# S6XT10W_MCU.net
KiCad netlist of a schematic drawn in Altium Designer
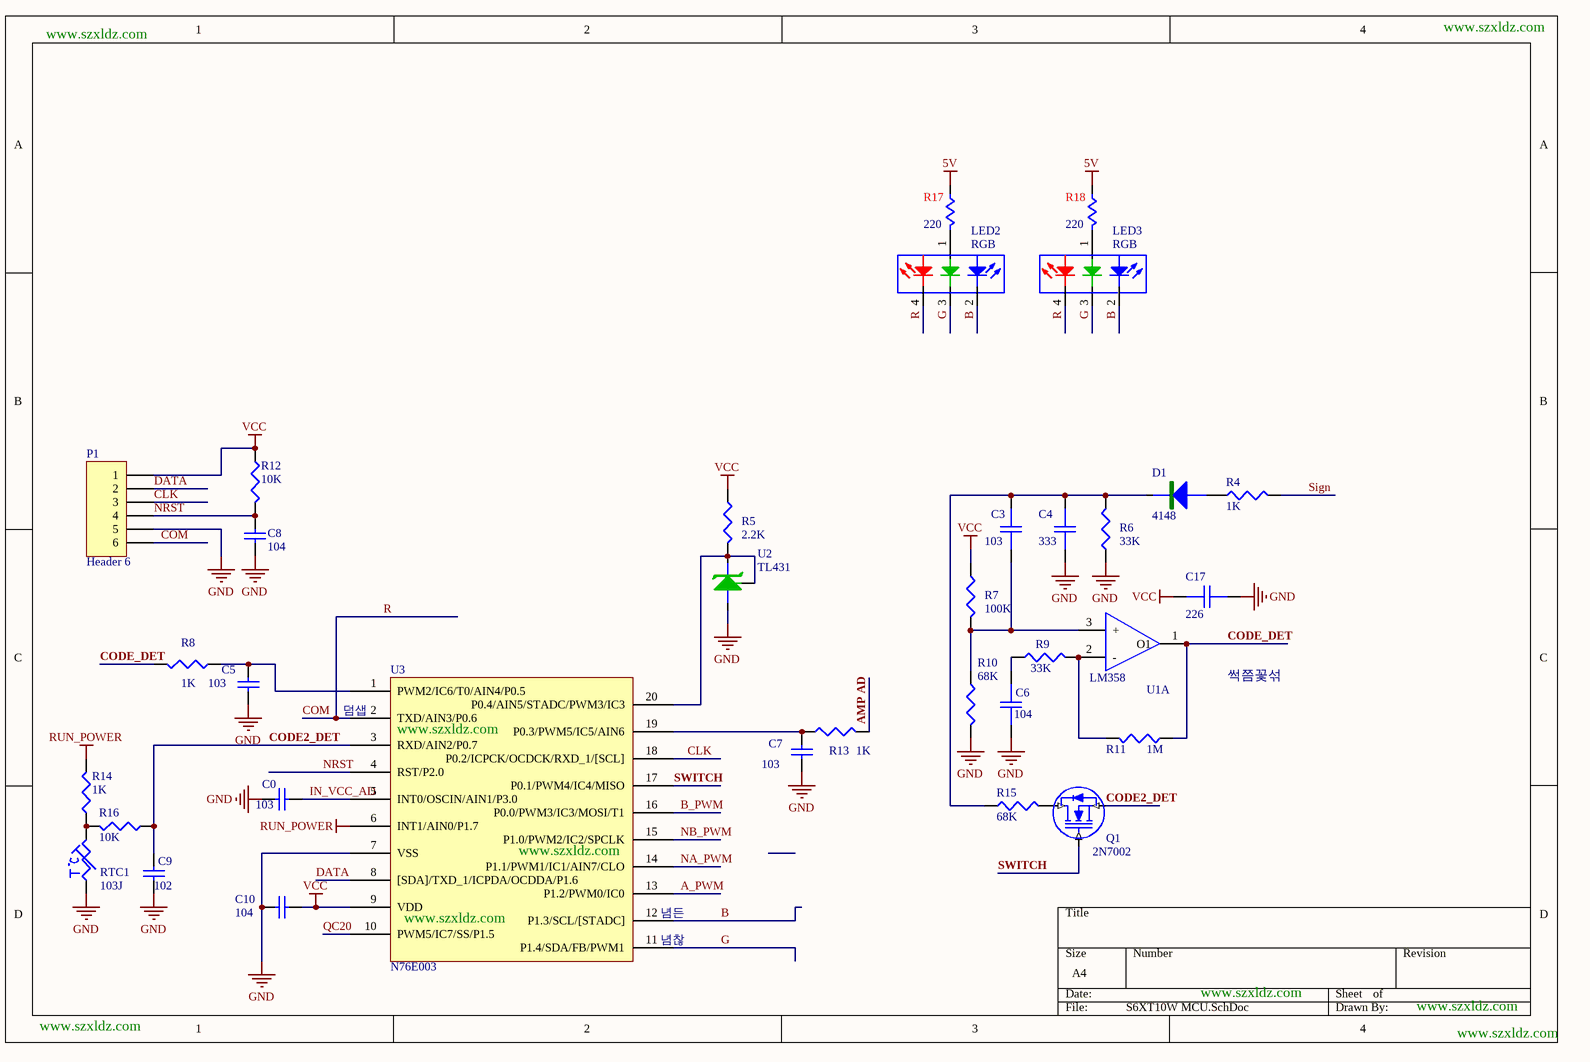
[diagram p0: S6XT10W MCU.SchDoc]

(export (version "E")
  (design (tool "Eeschema 10.0.6"))
  (components
    (comp (ref "C0")
      (value "103")
      (footprint "C0402")
      (description "Capacitor")
      (fields (field (name "PUBLISHER") "Altium Limited"))
      (libsource (lib "*") (part "Cap"))
    )
    (comp (ref "C3") (value "103") (footprint "C0402") (libsource (lib "*") (part "CH")))
    (comp (ref "C4") (value "333") (footprint "C0402") (libsource (lib "*") (part "CH")))
    (comp (ref "C5")
      (value "103")
      (footprint "C0402")
      (description "Capacitor")
      (fields (field (name "PUBLISHER") "Altium Limited"))
      (libsource (lib "*") (part "Cap"))
    )
    (comp (ref "C6") (value "104") (footprint "C0402") (libsource (lib "*") (part "CH")))
    (comp (ref "C7")
      (value "103")
      (footprint "C0402")
      (description "Capacitor")
      (fields (field (name "PUBLISHER") "Altium Limited"))
      (libsource (lib "*") (part "Cap"))
    )
    (comp (ref "C8")
      (value "104")
      (footprint "C0402")
      (description "Capacitor")
      (fields (field (name "PUBLISHER") "Altium Limited"))
      (libsource (lib "*") (part "Cap"))
    )
    (comp (ref "C9")
      (value "102")
      (footprint "C0402")
      (description "Capacitor")
      (fields (field (name "PUBLISHER") "Altium Limited"))
      (libsource (lib "*") (part "Cap"))
    )
    (comp (ref "C10")
      (value "104")
      (footprint "C0402")
      (description "Capacitor")
      (fields (field (name "PUBLISHER") "Altium Limited"))
      (libsource (lib "*") (part "Cap"))
    )
    (comp (ref "C17") (value "226") (footprint "C0805") (libsource (lib "*") (part "CH")))
    (comp (ref "D1")
      (value "4148")
      (footprint "sod323")
      (description "1N4001")
      (libsource (lib "*") (part "D0"))
    )
    (comp (ref "LED2") (value "RGB") (footprint "LED-RGB02") (libsource (lib "XiaoQiang") (part "LED05")))
    (comp (ref "LED3") (value "RGB") (footprint "LED-RGB02") (libsource (lib "XiaoQiang") (part "LED05")))
    (comp (ref "P1")
      (value "Header 6")
      (footprint "SPIN6")
      (description "Header, 6-Pin")
      (fields (field (name "PUBLISHER") "Altium Limited"))
      (libsource (lib "Miscellaneous Connectors") (part "Header 6"))
    )
    (comp (ref "Q1") (value "2N7002") (footprint "SOT-23B") (libsource (lib "lxzschlib") (part "MOSFETN")))
    (comp (ref "R4") (value "1K") (footprint "R0402") (libsource (lib "*") (part "R")))
    (comp (ref "R5") (value "2.2K") (footprint "R0402") (description "1K") (libsource (lib "*") (part "R")))
    (comp (ref "R6") (value "33K") (footprint "R0402") (description "1K") (libsource (lib "*") (part "R")))
    (comp (ref "R7") (value "100K") (footprint "R0402") (description "1K") (libsource (lib "*") (part "R")))
    (comp (ref "R8") (value "1K") (footprint "R0402") (libsource (lib "*") (part "R")))
    (comp (ref "R9") (value "33K") (footprint "R0402") (description "1K") (libsource (lib "*") (part "R")))
    (comp (ref "R10") (value "68K") (footprint "R0402") (description "1K") (libsource (lib "*") (part "R")))
    (comp (ref "R11") (value "1M") (footprint "R0402") (description "1K") (libsource (lib "*") (part "R")))
    (comp (ref "R12") (value "10K") (footprint "R0402") (libsource (lib "*") (part "R")))
    (comp (ref "R13") (value "1K") (footprint "R0402") (libsource (lib "*") (part "R")))
    (comp (ref "R14") (value "1K") (footprint "R0402") (libsource (lib "lxzschlib") (part "R")))
    (comp (ref "R15") (value "68K") (footprint "R0402") (description "1K") (libsource (lib "*") (part "R")))
    (comp (ref "R16")
      (value "10K")
      (footprint "R0402")
      (description "1K")
      (libsource (lib "lxzschlib") (part "R"))
    )
    (comp (ref "R17") (value "220") (footprint "R0402") (libsource (lib "XiaoQiang") (part "Res01")))
    (comp (ref "R18") (value "220") (footprint "R0402") (libsource (lib "XiaoQiang") (part "Res01")))
    (comp (ref "RTC1") (value "103J") (footprint "R0402") (libsource (lib "lxzschlib") (part "RTC")))
    (comp (ref "U1") (value "LM358") (footprint "SOP8") (libsource (lib "lxzschlib") (part "4558")))
    (comp (ref "U2")
      (value "TL431")
      (footprint "SOT-23-431")
      (description "IC")
      (libsource (lib "lxzschlib") (part "IC TL431"))
    )
    (comp (ref "U3") (value "N76E003") (footprint "SOP20") (libsource (lib "BEE802_V11") (part "103F")))
  )
  (nets
    (net (code "1") (name "/AMP AD") (class "Default") (node (ref "R13") (pin "2") (pintype "passive")))
    (net (code "2") (name "/A_PWM") (class "Default")
      (node (ref "U3") (pin "13") (pinfunction "P1.2/PWM0/IC0_13") (pintype "passive"))
    )
    (net (code "3") (name "/B") (class "Default")
      (node (ref "LED2") (pin "2") (pinfunction "A_2") (pintype "passive"))
      (node (ref "LED3") (pin "2") (pinfunction "A_2") (pintype "passive"))
      (node (ref "U3") (pin "12") (pinfunction "P1.3/SCL/[STADC]_12") (pintype "passive"))
    )
    (net (code "4") (name "/B_PWM") (class "Default")
      (node (ref "U3") (pin "16") (pinfunction "P0.0/PWM3/IC3/MOSI/T1_16") (pintype "passive"))
    )
    (net (code "5") (name "/CLK") (class "Default")
      (node (ref "P1") (pin "3") (pinfunction "3_3") (pintype "passive"))
      (node (ref "U3") (pin "18") (pinfunction "P0.2/ICPCK/OCDCK/RXD_1/[SCL]_18") (pintype "passive"))
    )
    (net (code "6") (name "/CODE2_DET") (class "Default")
      (node (ref "C9") (pin "2") (pinfunction "2_2") (pintype "passive"))
      (node (ref "Q1") (pin "E") (pinfunction "S_E") (pintype "input"))
      (node (ref "R16") (pin "1") (pintype "passive"))
      (node (ref "U3") (pin "3") (pinfunction "RXD/AIN2/P0.7_3") (pintype "passive"))
    )
    (net (code "7") (name "/CODE_DET") (class "Default")
      (node (ref "R11") (pin "1") (pintype "passive"))
      (node (ref "R8") (pin "2") (pintype "passive"))
      (node (ref "U1") (pin "1") (pinfunction "O1_1") (pintype "passive"))
    )
    (net (code "8") (name "/COM") (class "Default")
      (node (ref "LED2") (pin "4") (pinfunction "2_4") (pintype "passive"))
      (node (ref "LED3") (pin "4") (pinfunction "2_4") (pintype "passive"))
      (node (ref "P1") (pin "6") (pinfunction "6_6") (pintype "passive"))
      (node (ref "U3") (pin "2") (pinfunction "TXD/AIN3/P0.6_2") (pintype "passive"))
    )
    (net (code "9") (name "/DATA") (class "Default")
      (node (ref "P1") (pin "2") (pinfunction "2_2") (pintype "passive"))
      (node (ref "U3") (pin "8") (pinfunction "[SDA]/TXD_1/ICPDA/OCDDA/P1.6_8") (pintype "passive"))
    )
    (net (code "10") (name "/G") (class "Default")
      (node (ref "LED2") (pin "3") (pinfunction "2_3") (pintype "passive"))
      (node (ref "LED3") (pin "3") (pinfunction "2_3") (pintype "passive"))
      (node (ref "U3") (pin "11") (pinfunction "P1.4/SDA/FB/PWM1_11") (pintype "passive"))
    )
    (net (code "11") (name "/IN_VCC_AD") (class "Default")
      (node (ref "C0") (pin "2") (pinfunction "2_2") (pintype "passive"))
      (node (ref "U3") (pin "5") (pinfunction "INT0/OSCIN/AIN1/P3.0_5") (pintype "passive"))
    )
    (net (code "12") (name "/NA_PWM") (class "Default")
      (node (ref "U3") (pin "14") (pinfunction "P1.1/PWM1/IC1/AIN7/CLO_14") (pintype "passive"))
    )
    (net (code "13") (name "/NB_PWM") (class "Default")
      (node (ref "U3") (pin "15") (pinfunction "P1.0/PWM2/IC2/SPCLK_15") (pintype "passive"))
    )
    (net (code "14") (name "/NRST") (class "Default")
      (node (ref "C8") (pin "1") (pinfunction "1_1") (pintype "passive"))
      (node (ref "P1") (pin "4") (pinfunction "4_4") (pintype "passive"))
      (node (ref "R12") (pin "2") (pintype "passive"))
      (node (ref "U3") (pin "4") (pinfunction "RST/P2.0_4") (pintype "passive"))
    )
    (net (code "15") (name "/QC20") (class "Default")
      (node (ref "U3") (pin "10") (pinfunction "PWM5/IC7/SS/P1.5_10") (pintype "passive"))
    )
    (net (code "16") (name "/SWITCH") (class "Default")
      (node (ref "Q1") (pin "B") (pinfunction "G_B") (pintype "input"))
      (node (ref "U3") (pin "17") (pinfunction "P0.1/PWM4/IC4/MISO_17") (pintype "passive"))
    )
    (net (code "17") (name "/Sign") (class "Default") (node (ref "R4") (pin "2") (pintype "passive")))
    (net (code "18") (name "5V") (class "Default")
      (node (ref "R17") (pin "1") (pinfunction "1_1") (pintype "passive"))
      (node (ref "R18") (pin "1") (pinfunction "1_1") (pintype "passive"))
    )
    (net (code "19") (name "GND") (class "Default")
      (node (ref "C0") (pin "1") (pinfunction "1_1") (pintype "passive"))
      (node (ref "C10") (pin "1") (pinfunction "1_1") (pintype "passive"))
      (node (ref "C17") (pin "1") (pintype "passive"))
      (node (ref "C4") (pin "1") (pintype "passive"))
      (node (ref "C5") (pin "1") (pinfunction "1_1") (pintype "passive"))
      (node (ref "C6") (pin "1") (pintype "passive"))
      (node (ref "C7") (pin "2") (pinfunction "2_2") (pintype "passive"))
      (node (ref "C8") (pin "2") (pinfunction "2_2") (pintype "passive"))
      (node (ref "C9") (pin "1") (pinfunction "1_1") (pintype "passive"))
      (node (ref "P1") (pin "5") (pinfunction "5_5") (pintype "passive"))
      (node (ref "R10") (pin "2") (pintype "passive"))
      (node (ref "R6") (pin "1") (pintype "passive"))
      (node (ref "RTC1") (pin "1") (pintype "passive"))
      (node (ref "U2") (pin "1") (pintype "passive"))
      (node (ref "U3") (pin "7") (pinfunction "VSS_7") (pintype "passive"))
    )
    (net (code "20") (name "Net-(C3-Pad1)") (class "Default")
      (node (ref "C3") (pin "1") (pintype "passive"))
      (node (ref "C4") (pin "2") (pintype "passive"))
      (node (ref "D1") (pin "2") (pintype "passive"))
      (node (ref "R15") (pin "1") (pintype "passive"))
      (node (ref "R6") (pin "2") (pintype "passive"))
    )
    (net (code "21") (name "Net-(C6-Pad2)") (class "Default")
      (node (ref "C6") (pin "2") (pintype "passive"))
      (node (ref "R9") (pin "1") (pintype "passive"))
    )
    (net (code "22") (name "Net-(D1-Pad1)") (class "Default")
      (node (ref "D1") (pin "1") (pintype "passive"))
      (node (ref "R4") (pin "1") (pintype "passive"))
    )
    (net (code "23") (name "Net-(LED2-A-Pad1)") (class "Default")
      (node (ref "LED2") (pin "1") (pinfunction "A_1") (pintype "passive"))
      (node (ref "R17") (pin "2") (pinfunction "2_2") (pintype "passive"))
    )
    (net (code "24") (name "Net-(LED3-A-Pad1)") (class "Default")
      (node (ref "LED3") (pin "1") (pinfunction "A_1") (pintype "passive"))
      (node (ref "R18") (pin "2") (pinfunction "2_2") (pintype "passive"))
    )
    (net (code "25") (name "Net-(Q1-D)") (class "Default")
      (node (ref "Q1") (pin "C") (pinfunction "D_C") (pintype "input"))
      (node (ref "R15") (pin "2") (pintype "passive"))
    )
    (net (code "26") (name "Net-(R14-Pad1)") (class "Default")
      (node (ref "R14") (pin "1") (pintype "passive"))
      (node (ref "R16") (pin "2") (pintype "passive"))
      (node (ref "RTC1") (pin "2") (pintype "passive"))
    )
    (net (code "27") (name "Net-(U1A-+)") (class "Default")
      (node (ref "C3") (pin "2") (pintype "passive"))
      (node (ref "R10") (pin "1") (pintype "passive"))
      (node (ref "R7") (pin "2") (pintype "passive"))
      (node (ref "U1") (pin "3") (pinfunction "+_3") (pintype "passive"))
    )
    (net (code "28") (name "Net-(U1A--)") (class "Default")
      (node (ref "R11") (pin "2") (pintype "passive"))
      (node (ref "R9") (pin "2") (pintype "passive"))
      (node (ref "U1") (pin "2") (pinfunction "-_2") (pintype "passive"))
    )
    (net (code "29") (name "Net-(U3-P0.3{slash}PWM5{slash}IC5{slash}AIN6)") (class "Default")
      (node (ref "C7") (pin "1") (pinfunction "1_1") (pintype "passive"))
      (node (ref "R13") (pin "1") (pintype "passive"))
      (node (ref "U3") (pin "19") (pinfunction "P0.3/PWM5/IC5/AIN6_19") (pintype "passive"))
    )
    (net (code "30") (name "Net-(U3-P0.4{slash}AIN5{slash}STADC{slash}PWM3{slash}IC3)") (class "Default")
      (node (ref "R5") (pin "2") (pintype "passive"))
      (node (ref "U2") (pin "2") (pintype "passive"))
      (node (ref "U2") (pin "3") (pintype "passive"))
      (node (ref "U3") (pin "20") (pinfunction "P0.4/AIN5/STADC/PWM3/IC3_20") (pintype "passive"))
    )
    (net (code "31") (name "Net-(U3-PWM2{slash}IC6{slash}T0{slash}AIN4{slash}P0.5)") (class "Default")
      (node (ref "C5") (pin "2") (pinfunction "2_2") (pintype "passive"))
      (node (ref "R8") (pin "1") (pintype "passive"))
      (node (ref "U3") (pin "1") (pinfunction "PWM2/IC6/T0/AIN4/P0.5_1") (pintype "passive"))
    )
    (net (code "32") (name "RUN_POWER") (class "Default")
      (node (ref "R14") (pin "2") (pintype "passive"))
      (node (ref "U3") (pin "6") (pinfunction "INT1/AIN0/P1.7_6") (pintype "passive"))
    )
    (net (code "33") (name "VCC") (class "Default")
      (node (ref "C10") (pin "2") (pinfunction "2_2") (pintype "passive"))
      (node (ref "C17") (pin "2") (pintype "passive"))
      (node (ref "P1") (pin "1") (pinfunction "1_1") (pintype "passive"))
      (node (ref "R12") (pin "1") (pintype "passive"))
      (node (ref "R5") (pin "1") (pintype "passive"))
      (node (ref "R7") (pin "1") (pintype "passive"))
      (node (ref "U3") (pin "9") (pinfunction "VDD_9") (pintype "passive"))
    )
  )
)
